# Display.net
KiCad netlist of a schematic drawn in Altium Designer
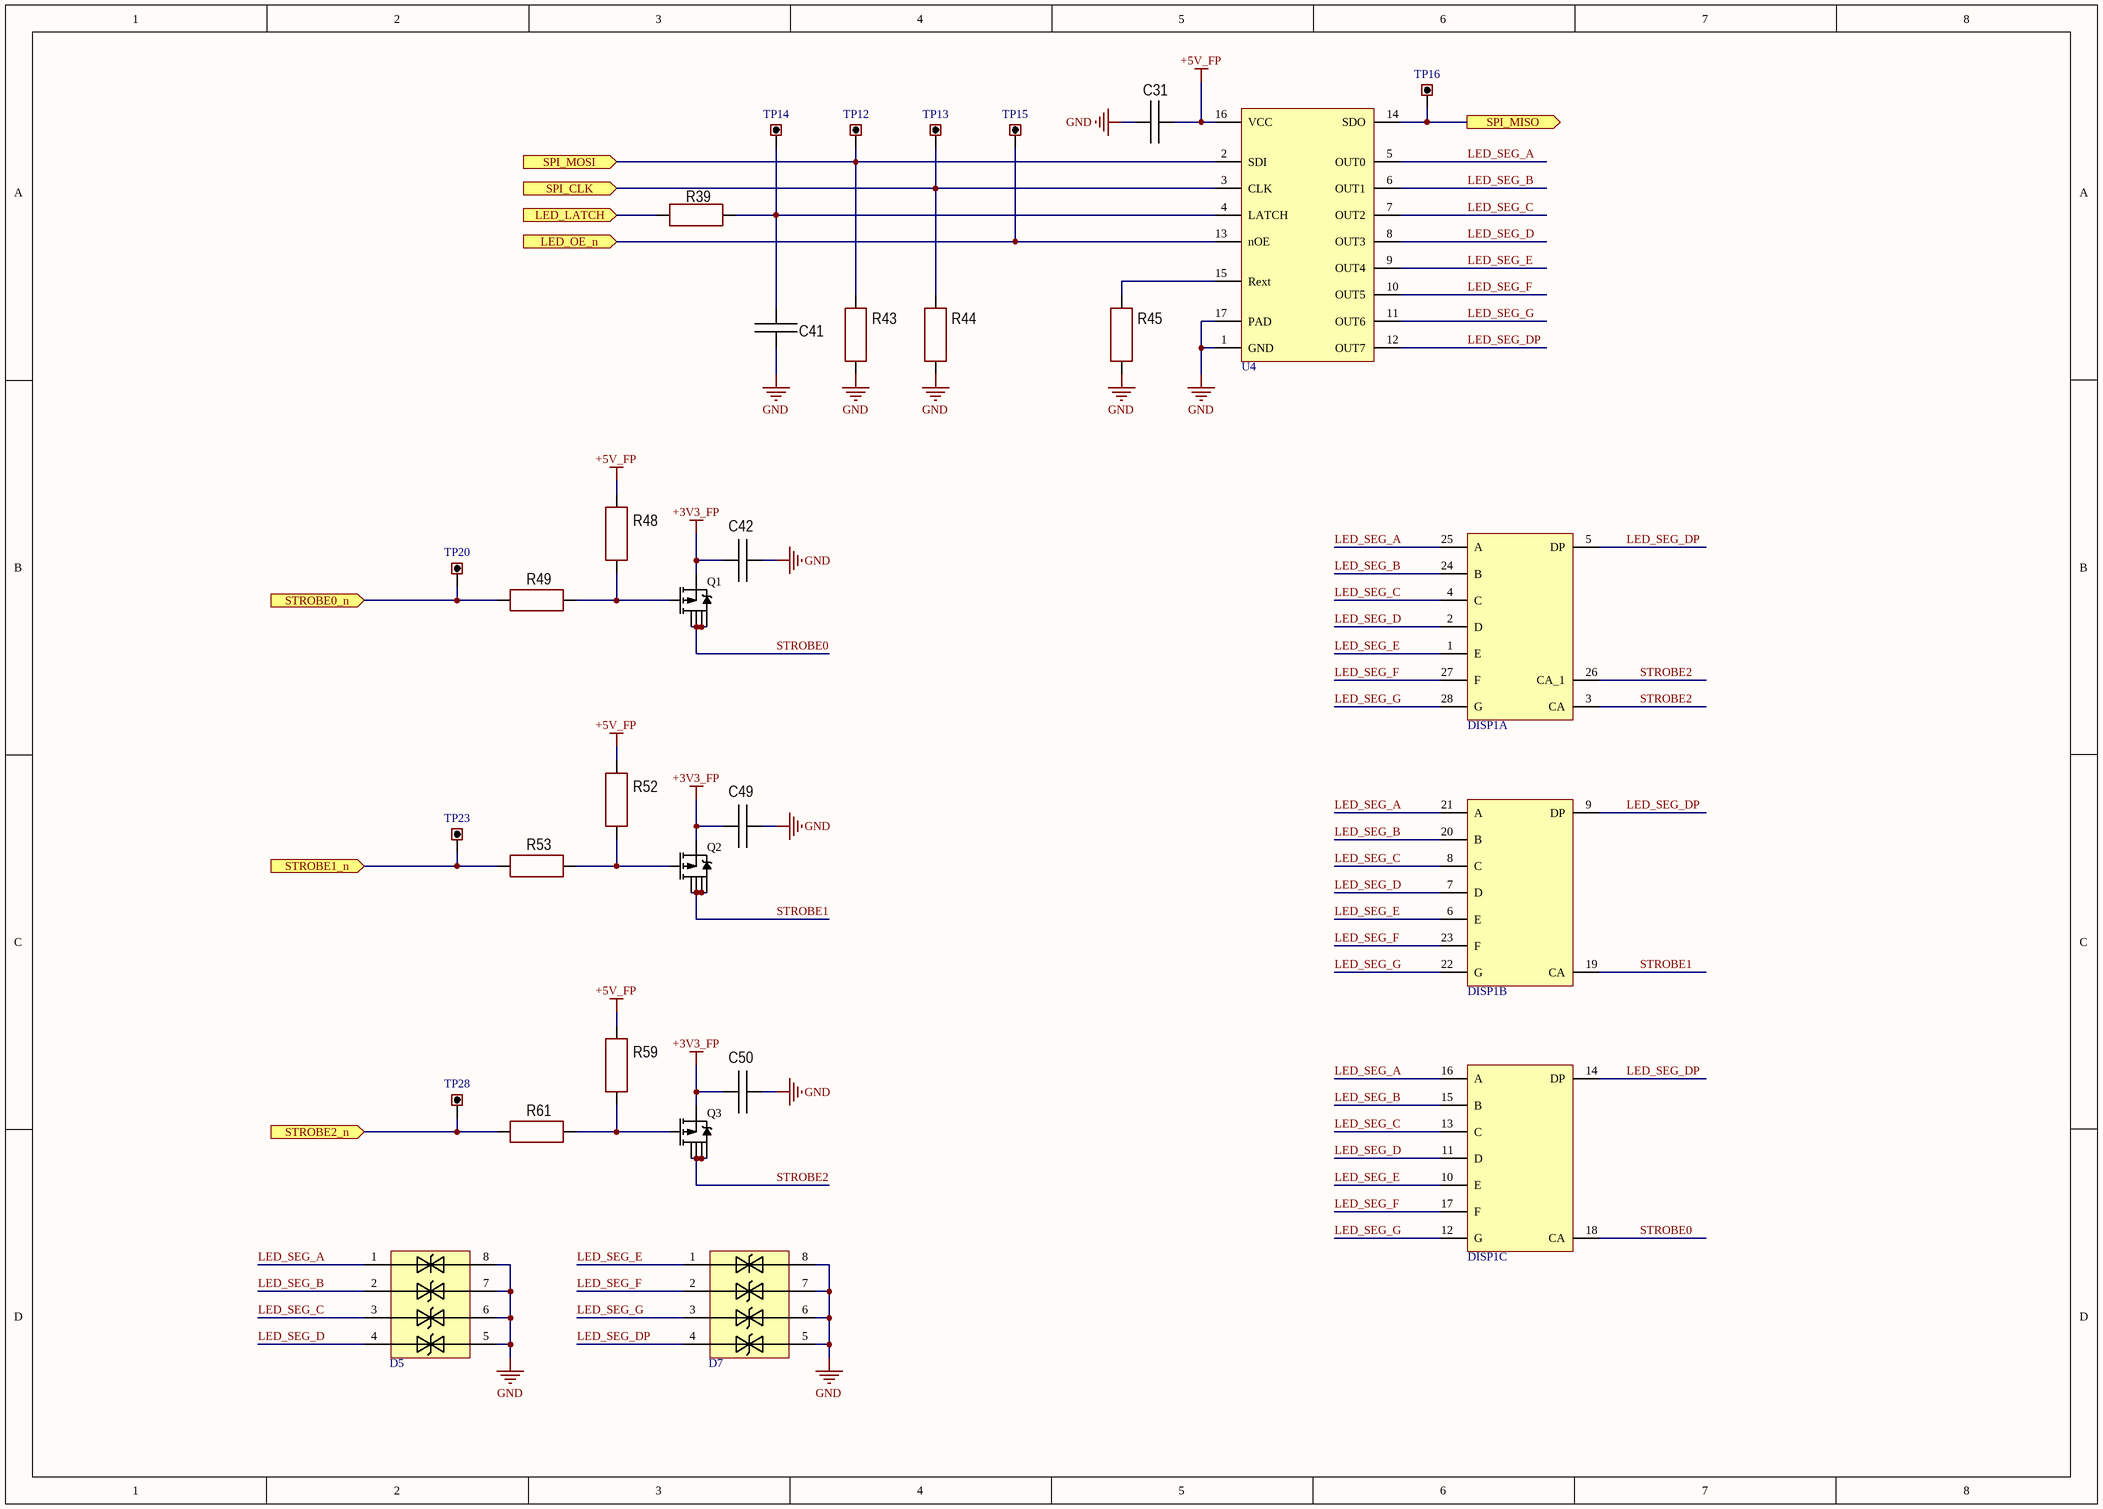
[diagram p0: Display.SchDoc]

(export (version "E")
  (design (tool "Eeschema 10.0.6"))
  (components
    (comp (ref "C31")
      (value "~")
      (footprint "StandardCase:CAP: 1206")
      (fields
        (field (name "MANUFACTURER") "Yageo")
        (field (name "PARTNUMBER") "CC1206KRX7R9BB104")
        (field (name "VALUEMANUFACTURERPARTNUMBER") "Ceramic capacitor, 0.1μF, 1206")
      )
      (libsource (lib "Capacitor") (part "Ceramic_1206"))
    )
    (comp (ref "C41")
      (value "~")
      (footprint "StandardCase:CAP: 1206")
      (fields
        (field (name "MANUFACTURER") "Yageo")
        (field (name "PARTNUMBER") "CC1206KRX7R9BB104")
        (field (name "VALUEMANUFACTURERPARTNUMBER") "Ceramic capacitor, 10nF, 1206")
      )
      (libsource (lib "Capacitor") (part "Ceramic_1206"))
    )
    (comp (ref "C42")
      (value "~")
      (footprint "StandardCase:CAP: 1206")
      (fields
        (field (name "MANUFACTURER") "Yageo")
        (field (name "PARTNUMBER") "CC1206KRX7R9BB104")
        (field (name "VALUEMANUFACTURERPARTNUMBER") "Ceramic capacitor, 0.1μF, 1206")
      )
      (libsource (lib "Capacitor") (part "Ceramic_1206"))
    )
    (comp (ref "C49")
      (value "~")
      (footprint "StandardCase:CAP: 1206")
      (fields
        (field (name "MANUFACTURER") "Yageo")
        (field (name "PARTNUMBER") "CC1206KRX7R9BB104")
        (field (name "VALUEMANUFACTURERPARTNUMBER") "Ceramic capacitor, 0.1μF, 1206")
      )
      (libsource (lib "Capacitor") (part "Ceramic_1206"))
    )
    (comp (ref "C50")
      (value "~")
      (footprint "StandardCase:CAP: 1206")
      (fields
        (field (name "MANUFACTURER") "Yageo")
        (field (name "PARTNUMBER") "CC1206KRX7R9BB104")
        (field (name "VALUEMANUFACTURERPARTNUMBER") "Ceramic capacitor, 0.1μF, 1206")
      )
      (libsource (lib "Capacitor") (part "Ceramic_1206"))
    )
    (comp (ref "D5")
      (value "~")
      (footprint "StandardCase:8-SOIC")
      (fields
        (field (name "VALUEMANUFACTURERPARTNUMBER") "CDNBS08-T05C, SOIC-8")
        (field (name "PARTNUMBER") "CDNBS08-T05C")
      )
      (libsource (lib "FP_lib_SCH") (part "CDNBS08-T05C"))
    )
    (comp (ref "D7")
      (value "~")
      (footprint "StandardCase:8-SOIC")
      (fields
        (field (name "VALUEMANUFACTURERPARTNUMBER") "CDNBS08-T05C, SOIC-8")
        (field (name "PARTNUMBER") "CDNBS08-T05C")
      )
      (libsource (lib "FP_lib_SCH") (part "CDNBS08-T05C"))
    )
    (comp (ref "DISP1")
      (value "~")
      (footprint "FP_lib_PCB:BC56-11SRWA")
      (fields
        (field (name "VALUEMANUFACTURERPARTNUMBER") "LED display, BA56-11SRWA")
        (field (name "PARTNUMBER") "BA56-11SRWA")
      )
      (libsource (lib "FP_lib_SCH") (part "BC56-11SRWA"))
    )
    (comp (ref "Q1")
      (value "~")
      (footprint "StandardCase:SOT23-6")
      (fields
        (field (name "VALUEMANUFACTURERPARTNUMBER") "DMP2067LVT, SOT23-6")
        (field (name "PARTNUMBER") "DMP2067LVT")
      )
      (libsource (lib "FP_lib_SCH") (part "DMP2067LVT"))
    )
    (comp (ref "Q2")
      (value "~")
      (footprint "StandardCase:SOT23-6")
      (fields
        (field (name "VALUEMANUFACTURERPARTNUMBER") "DMP2067LVT, SOT23-6")
        (field (name "PARTNUMBER") "DMP2067LVT")
      )
      (libsource (lib "FP_lib_SCH") (part "DMP2067LVT"))
    )
    (comp (ref "Q3")
      (value "~")
      (footprint "StandardCase:SOT23-6")
      (fields
        (field (name "VALUEMANUFACTURERPARTNUMBER") "DMP2067LVT, SOT23-6")
        (field (name "PARTNUMBER") "DMP2067LVT")
      )
      (libsource (lib "FP_lib_SCH") (part "DMP2067LVT"))
    )
    (comp (ref "R39")
      (value "~")
      (footprint "StandardCase:RES: 1206")
      (fields
        (field (name "MANUFACTURER") "Yageo")
        (field (name "PARTNUMBER") "RC1206JR-07100RL")
        (field (name "VALUEMANUFACTURERPARTNUMBER") "Resistor, 47R, 1206")
      )
      (libsource (lib "Resistor") (part "Resistor_1206"))
    )
    (comp (ref "R43")
      (value "~")
      (footprint "StandardCase:RES: 1206")
      (fields
        (field (name "MANUFACTURER") "Yageo")
        (field (name "PARTNUMBER") "RC1206JR-07100RL")
        (field (name "VALUEMANUFACTURERPARTNUMBER") "Resistor, 10K, 1206")
      )
      (libsource (lib "") (part "Resistor_1206_2"))
    )
    (comp (ref "R44")
      (value "~")
      (footprint "StandardCase:RES: 1206")
      (fields
        (field (name "MANUFACTURER") "Yageo")
        (field (name "PARTNUMBER") "RC1206JR-07100RL")
        (field (name "VALUEMANUFACTURERPARTNUMBER") "Resistor, 10K, 1206")
      )
      (libsource (lib "") (part "Resistor_1206_2"))
    )
    (comp (ref "R45")
      (value "~")
      (footprint "StandardCase:RES: 1206")
      (fields
        (field (name "MANUFACTURER") "Yageo")
        (field (name "PARTNUMBER") "RC1206JR-07100RL")
        (field (name "VALUEMANUFACTURERPARTNUMBER") "Resistor, 1K, 1206")
      )
      (libsource (lib "") (part "Resistor_1206_2"))
    )
    (comp (ref "R48")
      (value "~")
      (footprint "StandardCase:RES: 1206")
      (fields
        (field (name "MANUFACTURER") "Yageo")
        (field (name "PARTNUMBER") "RC1206JR-07100RL")
        (field (name "VALUEMANUFACTURERPARTNUMBER") "Resistor, 1K, 1206")
      )
      (libsource (lib "") (part "Resistor_1206_1"))
    )
    (comp (ref "R49")
      (value "~")
      (footprint "StandardCase:RES: 1206")
      (fields
        (field (name "MANUFACTURER") "Yageo")
        (field (name "PARTNUMBER") "RC1206JR-07100RL")
        (field (name "VALUEMANUFACTURERPARTNUMBER") "Resistor, 22.1R, 1206")
      )
      (libsource (lib "Resistor") (part "Resistor_1206"))
    )
    (comp (ref "R52")
      (value "~")
      (footprint "StandardCase:RES: 1206")
      (fields
        (field (name "MANUFACTURER") "Yageo")
        (field (name "PARTNUMBER") "RC1206JR-07100RL")
        (field (name "VALUEMANUFACTURERPARTNUMBER") "Resistor, 1K, 1206")
      )
      (libsource (lib "") (part "Resistor_1206_1"))
    )
    (comp (ref "R53")
      (value "~")
      (footprint "StandardCase:RES: 1206")
      (fields
        (field (name "MANUFACTURER") "Yageo")
        (field (name "PARTNUMBER") "RC1206JR-07100RL")
        (field (name "VALUEMANUFACTURERPARTNUMBER") "Resistor, 22.1R, 1206")
      )
      (libsource (lib "Resistor") (part "Resistor_1206"))
    )
    (comp (ref "R59")
      (value "~")
      (footprint "StandardCase:RES: 1206")
      (fields
        (field (name "MANUFACTURER") "Yageo")
        (field (name "PARTNUMBER") "RC1206JR-07100RL")
        (field (name "VALUEMANUFACTURERPARTNUMBER") "Resistor, 1K, 1206")
      )
      (libsource (lib "") (part "Resistor_1206_1"))
    )
    (comp (ref "R61")
      (value "~")
      (footprint "StandardCase:RES: 1206")
      (fields
        (field (name "MANUFACTURER") "Yageo")
        (field (name "PARTNUMBER") "RC1206JR-07100RL")
        (field (name "VALUEMANUFACTURERPARTNUMBER") "Resistor, 22.1R, 1206")
      )
      (libsource (lib "Resistor") (part "Resistor_1206"))
    )
    (comp (ref "TP12")
      (value "Test_Point")
      (footprint "FP_lib_PCB:Test_Point")
      (libsource (lib "FP_lib_SCH") (part "Test_Point"))
    )
    (comp (ref "TP13")
      (value "Test_Point")
      (footprint "FP_lib_PCB:Test_Point")
      (libsource (lib "FP_lib_SCH") (part "Test_Point"))
    )
    (comp (ref "TP14")
      (value "Test_Point")
      (footprint "FP_lib_PCB:Test_Point")
      (libsource (lib "FP_lib_SCH") (part "Test_Point"))
    )
    (comp (ref "TP15")
      (value "Test_Point")
      (footprint "FP_lib_PCB:Test_Point")
      (libsource (lib "FP_lib_SCH") (part "Test_Point"))
    )
    (comp (ref "TP16")
      (value "Test_Point")
      (footprint "FP_lib_PCB:Test_Point")
      (libsource (lib "FP_lib_SCH") (part "Test_Point"))
    )
    (comp (ref "TP20")
      (value "Test_Point")
      (footprint "FP_lib_PCB:Test_Point")
      (libsource (lib "FP_lib_SCH") (part "Test_Point"))
    )
    (comp (ref "TP23")
      (value "Test_Point")
      (footprint "FP_lib_PCB:Test_Point")
      (libsource (lib "FP_lib_SCH") (part "Test_Point"))
    )
    (comp (ref "TP28")
      (value "Test_Point")
      (footprint "FP_lib_PCB:Test_Point")
      (libsource (lib "FP_lib_SCH") (part "Test_Point"))
    )
    (comp (ref "U4")
      (value "~")
      (footprint "FP_lib_PCB:STP08DP05")
      (fields
        (field (name "VALUEMANUFACTURERPARTNUMBER") "STP08DP05, TSOP-16")
        (field (name "PARTNUMBER") "STP08DP05")
      )
      (libsource (lib "FP_lib_SCH") (part "STP08DP05"))
    )
  )
  (nets
    (net (code "1") (name "+3V3_FP") (class "Default")
      (node (ref "C42") (pin "1") (pinfunction "1_1") (pintype "power_in"))
      (node (ref "C49") (pin "1") (pinfunction "1_1") (pintype "power_in"))
      (node (ref "C50") (pin "1") (pinfunction "1_1") (pintype "power_in"))
      (node (ref "Q1") (pin "4") (pinfunction "S_4") (pintype "passive"))
      (node (ref "Q2") (pin "4") (pinfunction "S_4") (pintype "passive"))
      (node (ref "Q3") (pin "4") (pinfunction "S_4") (pintype "passive"))
    )
    (net (code "2") (name "+5V_FP") (class "Default")
      (node (ref "C31") (pin "2") (pinfunction "2_2") (pintype "power_in"))
      (node (ref "R48") (pin "2") (pinfunction "2_2") (pintype "passive"))
      (node (ref "R52") (pin "2") (pinfunction "2_2") (pintype "passive"))
      (node (ref "R59") (pin "2") (pinfunction "2_2") (pintype "passive"))
      (node (ref "U4") (pin "16") (pinfunction "VCC_16") (pintype "passive"))
    )
    (net (code "3") (name "/LED_LATCH") (class "Default")
      (node (ref "R39") (pin "1") (pinfunction "1_1") (pintype "passive"))
    )
    (net (code "4") (name "/LED_OE_n") (class "Default")
      (node (ref "TP15") (pin "1") (pinfunction "1_1") (pintype "passive"))
      (node (ref "U4") (pin "13") (pinfunction "nOE_13") (pintype "passive"))
    )
    (net (code "5") (name "/LED_SEG_A") (class "Default")
      (node (ref "D5") (pin "1") (pintype "passive"))
      (node (ref "DISP1") (pin "16") (pinfunction "A_16") (pintype "passive"))
      (node (ref "DISP1") (pin "21") (pinfunction "A_21") (pintype "passive"))
      (node (ref "DISP1") (pin "25") (pinfunction "A_25") (pintype "passive"))
      (node (ref "U4") (pin "5") (pinfunction "OUT0_5") (pintype "passive"))
    )
    (net (code "6") (name "/LED_SEG_B") (class "Default")
      (node (ref "D5") (pin "2") (pintype "passive"))
      (node (ref "DISP1") (pin "15") (pinfunction "B_15") (pintype "passive"))
      (node (ref "DISP1") (pin "20") (pinfunction "B_20") (pintype "passive"))
      (node (ref "DISP1") (pin "24") (pinfunction "B_24") (pintype "passive"))
      (node (ref "U4") (pin "6") (pinfunction "OUT1_6") (pintype "passive"))
    )
    (net (code "7") (name "/LED_SEG_C") (class "Default")
      (node (ref "D5") (pin "3") (pintype "passive"))
      (node (ref "DISP1") (pin "13") (pinfunction "C_13") (pintype "passive"))
      (node (ref "DISP1") (pin "4") (pinfunction "C_4") (pintype "passive"))
      (node (ref "DISP1") (pin "8") (pinfunction "C_8") (pintype "passive"))
      (node (ref "U4") (pin "7") (pinfunction "OUT2_7") (pintype "passive"))
    )
    (net (code "8") (name "/LED_SEG_D") (class "Default")
      (node (ref "D5") (pin "4") (pintype "passive"))
      (node (ref "DISP1") (pin "11") (pinfunction "D_11") (pintype "passive"))
      (node (ref "DISP1") (pin "2") (pinfunction "D_2") (pintype "passive"))
      (node (ref "DISP1") (pin "7") (pinfunction "D_7") (pintype "passive"))
      (node (ref "U4") (pin "8") (pinfunction "OUT3_8") (pintype "passive"))
    )
    (net (code "9") (name "/LED_SEG_DP") (class "Default")
      (node (ref "D7") (pin "4") (pintype "passive"))
      (node (ref "DISP1") (pin "14") (pinfunction "DP_14") (pintype "passive"))
      (node (ref "DISP1") (pin "5") (pinfunction "DP_5") (pintype "passive"))
      (node (ref "DISP1") (pin "9") (pinfunction "DP_9") (pintype "passive"))
      (node (ref "U4") (pin "12") (pinfunction "OUT7_12") (pintype "passive"))
    )
    (net (code "10") (name "/LED_SEG_E") (class "Default")
      (node (ref "D7") (pin "1") (pintype "passive"))
      (node (ref "DISP1") (pin "1") (pinfunction "E_1") (pintype "passive"))
      (node (ref "DISP1") (pin "10") (pinfunction "E_10") (pintype "passive"))
      (node (ref "DISP1") (pin "6") (pinfunction "E_6") (pintype "passive"))
      (node (ref "U4") (pin "9") (pinfunction "OUT4_9") (pintype "passive"))
    )
    (net (code "11") (name "/LED_SEG_F") (class "Default")
      (node (ref "D7") (pin "2") (pintype "passive"))
      (node (ref "DISP1") (pin "17") (pinfunction "F_17") (pintype "passive"))
      (node (ref "DISP1") (pin "23") (pinfunction "F_23") (pintype "passive"))
      (node (ref "DISP1") (pin "27") (pinfunction "F_27") (pintype "passive"))
      (node (ref "U4") (pin "10") (pinfunction "OUT5_10") (pintype "passive"))
    )
    (net (code "12") (name "/LED_SEG_G") (class "Default")
      (node (ref "D7") (pin "3") (pintype "passive"))
      (node (ref "DISP1") (pin "12") (pinfunction "G_12") (pintype "passive"))
      (node (ref "DISP1") (pin "22") (pinfunction "G_22") (pintype "passive"))
      (node (ref "DISP1") (pin "28") (pinfunction "G_28") (pintype "passive"))
      (node (ref "U4") (pin "11") (pinfunction "OUT6_11") (pintype "passive"))
    )
    (net (code "13") (name "/SPI_CLK") (class "Default")
      (node (ref "R44") (pin "1") (pinfunction "1_1") (pintype "passive"))
      (node (ref "TP13") (pin "1") (pinfunction "1_1") (pintype "passive"))
      (node (ref "U4") (pin "3") (pinfunction "CLK_3") (pintype "passive"))
    )
    (net (code "14") (name "/SPI_MISO") (class "Default")
      (node (ref "TP16") (pin "1") (pinfunction "1_1") (pintype "passive"))
      (node (ref "U4") (pin "14") (pinfunction "SDO_14") (pintype "passive"))
    )
    (net (code "15") (name "/SPI_MOSI") (class "Default")
      (node (ref "R43") (pin "1") (pinfunction "1_1") (pintype "passive"))
      (node (ref "TP12") (pin "1") (pinfunction "1_1") (pintype "passive"))
      (node (ref "U4") (pin "2") (pinfunction "SDI_2") (pintype "passive"))
    )
    (net (code "16") (name "/STROBE0") (class "Default")
      (node (ref "DISP1") (pin "18") (pinfunction "CA_18") (pintype "passive"))
      (node (ref "Q1") (pin "1") (pinfunction "D_1") (pintype "passive"))
      (node (ref "Q1") (pin "2") (pinfunction "D_2") (pintype "passive"))
      (node (ref "Q1") (pin "5") (pinfunction "D_5") (pintype "passive"))
      (node (ref "Q1") (pin "6") (pinfunction "D_6") (pintype "passive"))
    )
    (net (code "17") (name "/STROBE0_n") (class "Default")
      (node (ref "R49") (pin "1") (pinfunction "1_1") (pintype "passive"))
      (node (ref "TP20") (pin "1") (pinfunction "1_1") (pintype "passive"))
    )
    (net (code "18") (name "/STROBE1") (class "Default")
      (node (ref "DISP1") (pin "19") (pinfunction "CA_19") (pintype "passive"))
      (node (ref "Q2") (pin "1") (pinfunction "D_1") (pintype "passive"))
      (node (ref "Q2") (pin "2") (pinfunction "D_2") (pintype "passive"))
      (node (ref "Q2") (pin "5") (pinfunction "D_5") (pintype "passive"))
      (node (ref "Q2") (pin "6") (pinfunction "D_6") (pintype "passive"))
    )
    (net (code "19") (name "/STROBE1_n") (class "Default")
      (node (ref "R53") (pin "1") (pinfunction "1_1") (pintype "passive"))
      (node (ref "TP23") (pin "1") (pinfunction "1_1") (pintype "passive"))
    )
    (net (code "20") (name "/STROBE2") (class "Default")
      (node (ref "DISP1") (pin "26") (pinfunction "CA_1_26") (pintype "passive"))
      (node (ref "DISP1") (pin "3") (pinfunction "CA_3") (pintype "passive"))
      (node (ref "Q3") (pin "1") (pinfunction "D_1") (pintype "passive"))
      (node (ref "Q3") (pin "2") (pinfunction "D_2") (pintype "passive"))
      (node (ref "Q3") (pin "5") (pinfunction "D_5") (pintype "passive"))
      (node (ref "Q3") (pin "6") (pinfunction "D_6") (pintype "passive"))
    )
    (net (code "21") (name "/STROBE2_n") (class "Default")
      (node (ref "R61") (pin "1") (pinfunction "1_1") (pintype "passive"))
      (node (ref "TP28") (pin "1") (pinfunction "1_1") (pintype "passive"))
    )
    (net (code "22") (name "GND") (class "Default")
      (node (ref "C31") (pin "1") (pinfunction "1_1") (pintype "power_in"))
      (node (ref "C41") (pin "1") (pinfunction "1_1") (pintype "power_in"))
      (node (ref "C42") (pin "2") (pinfunction "2_2") (pintype "power_in"))
      (node (ref "C49") (pin "2") (pinfunction "2_2") (pintype "power_in"))
      (node (ref "C50") (pin "2") (pinfunction "2_2") (pintype "power_in"))
      (node (ref "D5") (pin "5") (pintype "passive"))
      (node (ref "D5") (pin "6") (pintype "passive"))
      (node (ref "D5") (pin "7") (pintype "passive"))
      (node (ref "D5") (pin "8") (pintype "passive"))
      (node (ref "D7") (pin "5") (pintype "passive"))
      (node (ref "D7") (pin "6") (pintype "passive"))
      (node (ref "D7") (pin "7") (pintype "passive"))
      (node (ref "D7") (pin "8") (pintype "passive"))
      (node (ref "R43") (pin "2") (pinfunction "2_2") (pintype "passive"))
      (node (ref "R44") (pin "2") (pinfunction "2_2") (pintype "passive"))
      (node (ref "R45") (pin "2") (pinfunction "2_2") (pintype "passive"))
      (node (ref "U4") (pin "1") (pinfunction "GND_1") (pintype "passive"))
      (node (ref "U4") (pin "17") (pinfunction "PAD_17") (pintype "passive"))
    )
    (net (code "23") (name "Net-(Q1-G)") (class "Default")
      (node (ref "Q1") (pin "3") (pinfunction "G_3") (pintype "passive"))
      (node (ref "R48") (pin "1") (pinfunction "1_1") (pintype "passive"))
      (node (ref "R49") (pin "2") (pinfunction "2_2") (pintype "passive"))
    )
    (net (code "24") (name "Net-(Q2-G)") (class "Default")
      (node (ref "Q2") (pin "3") (pinfunction "G_3") (pintype "passive"))
      (node (ref "R52") (pin "1") (pinfunction "1_1") (pintype "passive"))
      (node (ref "R53") (pin "2") (pinfunction "2_2") (pintype "passive"))
    )
    (net (code "25") (name "Net-(Q3-G)") (class "Default")
      (node (ref "Q3") (pin "3") (pinfunction "G_3") (pintype "passive"))
      (node (ref "R59") (pin "1") (pinfunction "1_1") (pintype "passive"))
      (node (ref "R61") (pin "2") (pinfunction "2_2") (pintype "passive"))
    )
    (net (code "26") (name "Net-(U4-LATCH)") (class "Default")
      (node (ref "C41") (pin "2") (pinfunction "2_2") (pintype "power_in"))
      (node (ref "R39") (pin "2") (pinfunction "2_2") (pintype "passive"))
      (node (ref "TP14") (pin "1") (pinfunction "1_1") (pintype "passive"))
      (node (ref "U4") (pin "4") (pinfunction "LATCH_4") (pintype "passive"))
    )
    (net (code "27") (name "Net-(U4-Rext)") (class "Default")
      (node (ref "R45") (pin "1") (pinfunction "1_1") (pintype "passive"))
      (node (ref "U4") (pin "15") (pinfunction "Rext_15") (pintype "passive"))
    )
  )
)
